# v1.net
KiCad netlist of a schematic drawn in EAGLE
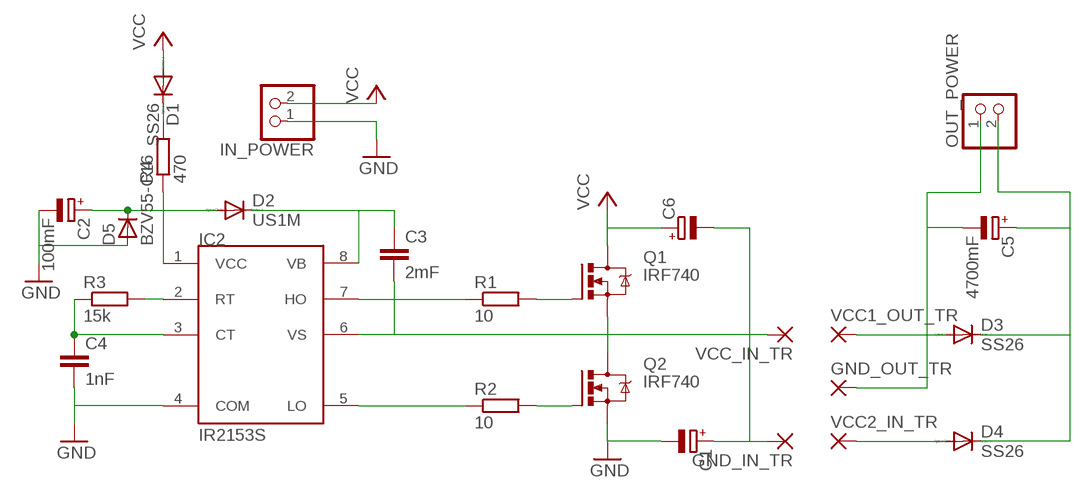
[diagram p0: schematic, sheet 1]

(export (version "E")
  (design (tool "Eeschema 10.0.6"))
  (components
    (comp (ref "C1")
      (value "CPOL-EUE10-22.5")
      (footprint "eagle-import:EB22,5D")
      (libsource (lib "eagle-import") (part "CPOL-EUE10-22.5"))
    )
    (comp (ref "C2")
      (value "100mF")
      (footprint "eagle-import:PANASONIC_C")
      (libsource (lib "eagle-import") (part "CPOL-EUC"))
    )
    (comp (ref "C3")
      (value "2mF")
      (footprint "eagle-import:C0805")
      (libsource (lib "eagle-import") (part "C-EUC0805"))
    )
    (comp (ref "C4")
      (value "1nF")
      (footprint "eagle-import:C0805")
      (libsource (lib "eagle-import") (part "C-EUC0805"))
    )
    (comp (ref "C5")
      (value "4700mF")
      (footprint "eagle-import:E7,5-18")
      (libsource (lib "eagle-import") (part "CPOL-EUE7.5-18"))
    )
    (comp (ref "C6")
      (value "CPOL-EUE10-22.5")
      (footprint "eagle-import:EB22,5D")
      (libsource (lib "eagle-import") (part "CPOL-EUE10-22.5"))
    )
    (comp (ref "D1")
      (value "SS26")
      (footprint "eagle-import:DO-214AC")
      (libsource (lib "eagle-import") (part "DIODE-DO-214AC"))
    )
    (comp (ref "D2")
      (value "US1M")
      (footprint "eagle-import:DO-214AC")
      (libsource (lib "eagle-import") (part "DIODE-DO-214AC"))
    )
    (comp (ref "D3")
      (value "SS26")
      (footprint "eagle-import:DO-214AC")
      (libsource (lib "eagle-import") (part "DIODE-DO-214AC"))
    )
    (comp (ref "D4")
      (value "SS26")
      (footprint "eagle-import:DO-214AC")
      (libsource (lib "eagle-import") (part "DIODE-DO-214AC"))
    )
    (comp (ref "D5")
      (value "BZV55-C16")
      (footprint "eagle-import:SOD80")
      (libsource (lib "eagle-import") (part "D-SOD-80"))
    )
    (comp (ref "GND_IN_TR")
      (value "1,6/0,8")
      (footprint "eagle-import:1,6_0,8")
      (libsource (lib "eagle-import") (part "1,6/0,8"))
    )
    (comp (ref "GND_OUT_TR")
      (value "1,6/0,8")
      (footprint "eagle-import:1,6_0,8")
      (libsource (lib "eagle-import") (part "1,6/0,8"))
    )
    (comp (ref "IC2")
      (value "IR2153S")
      (footprint "eagle-import:SO08")
      (libsource (lib "eagle-import") (part "IR2153S"))
    )
    (comp (ref "IN_POWER")
      (value "PINHD-1X2")
      (footprint "eagle-import:1X02")
      (libsource (lib "eagle-import") (part "PINHD-1X2"))
    )
    (comp (ref "OUT_POWER")
      (value "PINHD-1X2")
      (footprint "eagle-import:1X02")
      (libsource (lib "eagle-import") (part "PINHD-1X2"))
    )
    (comp (ref "Q1")
      (value "IRF740")
      (footprint "eagle-import:TO220BV")
      (libsource (lib "eagle-import") (part "IRF740"))
    )
    (comp (ref "Q2")
      (value "IRF740")
      (footprint "eagle-import:TO220BV")
      (libsource (lib "eagle-import") (part "IRF740"))
    )
    (comp (ref "R1")
      (value "10")
      (footprint "eagle-import:R0805")
      (libsource (lib "eagle-import") (part "R-EU_R0805"))
    )
    (comp (ref "R2")
      (value "10")
      (footprint "eagle-import:R0805")
      (libsource (lib "eagle-import") (part "R-EU_R0805"))
    )
    (comp (ref "R3")
      (value "15k")
      (footprint "eagle-import:R0805")
      (libsource (lib "eagle-import") (part "R-EU_R0805"))
    )
    (comp (ref "R4")
      (value "470")
      (footprint "eagle-import:R0805")
      (libsource (lib "eagle-import") (part "R-EU_R0805"))
    )
    (comp (ref "VCC1_OUT_TR")
      (value "1,6/0,8")
      (footprint "eagle-import:1,6_0,8")
      (libsource (lib "eagle-import") (part "1,6/0,8"))
    )
    (comp (ref "VCC2_IN_TR")
      (value "1,6/0,8")
      (footprint "eagle-import:1,6_0,8")
      (libsource (lib "eagle-import") (part "1,6/0,8"))
    )
    (comp (ref "VCC_IN_TR")
      (value "1,6/0,8")
      (footprint "eagle-import:1,6_0,8")
      (libsource (lib "eagle-import") (part "1,6/0,8"))
    )
  )
  (nets
    (net (code "1") (name "GND") (class "Default")
      (node (ref "C1") (pin "-") (pinfunction "-_-") (pintype "passive"))
      (node (ref "C2") (pin "-") (pinfunction "-_-") (pintype "passive"))
      (node (ref "C4") (pin "2") (pinfunction "2_2") (pintype "passive"))
      (node (ref "D5") (pin "2") (pinfunction "A_2") (pintype "passive"))
      (node (ref "IC2") (pin "4") (pinfunction "COM_4") (pintype "power_in"))
      (node (ref "IN_POWER") (pin "1") (pinfunction "1_1") (pintype "passive"))
      (node (ref "Q2") (pin "S") (pinfunction "S_S") (pintype "passive"))
    )
    (net (code "2") (name "Net-(C5-Pad+)") (class "Default")
      (node (ref "C5") (pin "+") (pinfunction "+_+") (pintype "passive"))
      (node (ref "D3") (pin "C") (pinfunction "C_C") (pintype "passive"))
      (node (ref "D4") (pin "C") (pinfunction "C_C") (pintype "passive"))
      (node (ref "OUT_POWER") (pin "2") (pinfunction "2_2") (pintype "passive"))
    )
    (net (code "3") (name "Net-(D1-PadC)") (class "Default")
      (node (ref "D1") (pin "C") (pinfunction "C_C") (pintype "passive"))
      (node (ref "R4") (pin "2") (pinfunction "2_2") (pintype "passive"))
    )
    (net (code "4") (name "Net-(D5-C)") (class "Default")
      (node (ref "C2") (pin "+") (pinfunction "+_+") (pintype "passive"))
      (node (ref "D2") (pin "A") (pinfunction "A_A") (pintype "passive"))
      (node (ref "D5") (pin "1") (pinfunction "C_1") (pintype "passive"))
      (node (ref "IC2") (pin "1") (pinfunction "VCC_1") (pintype "power_in"))
      (node (ref "R4") (pin "1") (pinfunction "1_1") (pintype "passive"))
    )
    (net (code "5") (name "Net-(GND_IN_TR-P)") (class "Default")
      (node (ref "C1") (pin "+") (pinfunction "+_+") (pintype "passive"))
      (node (ref "C6") (pin "-") (pinfunction "-_-") (pintype "passive"))
      (node (ref "GND_IN_TR") (pin "1") (pinfunction "P_1") (pintype "passive"))
    )
    (net (code "6") (name "Net-(GND_OUT_TR-P)") (class "Default")
      (node (ref "C5") (pin "-") (pinfunction "-_-") (pintype "passive"))
      (node (ref "GND_OUT_TR") (pin "1") (pinfunction "P_1") (pintype "passive"))
      (node (ref "OUT_POWER") (pin "1") (pinfunction "1_1") (pintype "passive"))
    )
    (net (code "7") (name "Net-(IC2-CT)") (class "Default")
      (node (ref "C4") (pin "1") (pinfunction "1_1") (pintype "passive"))
      (node (ref "IC2") (pin "3") (pinfunction "CT_3") (pintype "input"))
      (node (ref "R3") (pin "1") (pinfunction "1_1") (pintype "passive"))
    )
    (net (code "8") (name "Net-(IC2-HO)") (class "Default")
      (node (ref "IC2") (pin "7") (pinfunction "HO_7") (pintype "output"))
      (node (ref "R1") (pin "1") (pinfunction "1_1") (pintype "passive"))
    )
    (net (code "9") (name "Net-(IC2-LO)") (class "Default")
      (node (ref "IC2") (pin "5") (pinfunction "LO_5") (pintype "output"))
      (node (ref "R2") (pin "1") (pinfunction "1_1") (pintype "passive"))
    )
    (net (code "10") (name "Net-(IC2-RT)") (class "Default")
      (node (ref "IC2") (pin "2") (pinfunction "RT_2") (pintype "output"))
      (node (ref "R3") (pin "2") (pinfunction "2_2") (pintype "passive"))
    )
    (net (code "11") (name "Net-(IC2-VB)") (class "Default")
      (node (ref "C3") (pin "1") (pinfunction "1_1") (pintype "passive"))
      (node (ref "D2") (pin "C") (pinfunction "C_C") (pintype "passive"))
      (node (ref "IC2") (pin "8") (pinfunction "VB_8") (pintype "power_in"))
    )
    (net (code "12") (name "Net-(IC2-VS)") (class "Default")
      (node (ref "C3") (pin "2") (pinfunction "2_2") (pintype "passive"))
      (node (ref "IC2") (pin "6") (pinfunction "VS_6") (pintype "power_in"))
      (node (ref "Q1") (pin "S") (pinfunction "S_S") (pintype "passive"))
      (node (ref "Q2") (pin "D") (pinfunction "D_D") (pintype "passive"))
      (node (ref "VCC_IN_TR") (pin "1") (pinfunction "P_1") (pintype "passive"))
    )
    (net (code "13") (name "Net-(Q1-PadG)") (class "Default")
      (node (ref "Q1") (pin "G") (pinfunction "G_G") (pintype "passive"))
      (node (ref "R1") (pin "2") (pinfunction "2_2") (pintype "passive"))
    )
    (net (code "14") (name "Net-(Q2-PadG)") (class "Default")
      (node (ref "Q2") (pin "G") (pinfunction "G_G") (pintype "passive"))
      (node (ref "R2") (pin "2") (pinfunction "2_2") (pintype "passive"))
    )
    (net (code "15") (name "Net-(VCC1_OUT_TR-P)") (class "Default")
      (node (ref "D3") (pin "A") (pinfunction "A_A") (pintype "passive"))
      (node (ref "VCC1_OUT_TR") (pin "1") (pinfunction "P_1") (pintype "passive"))
    )
    (net (code "16") (name "Net-(VCC2_IN_TR-P)") (class "Default")
      (node (ref "D4") (pin "A") (pinfunction "A_A") (pintype "passive"))
      (node (ref "VCC2_IN_TR") (pin "1") (pinfunction "P_1") (pintype "passive"))
    )
    (net (code "17") (name "VCC") (class "Default")
      (node (ref "C6") (pin "+") (pinfunction "+_+") (pintype "passive"))
      (node (ref "D1") (pin "A") (pinfunction "A_A") (pintype "passive"))
      (node (ref "IN_POWER") (pin "2") (pinfunction "2_2") (pintype "passive"))
      (node (ref "Q1") (pin "D") (pinfunction "D_D") (pintype "passive"))
    )
  )
)
